# shield3.net
KiCad netlist of a schematic drawn in EAGLE
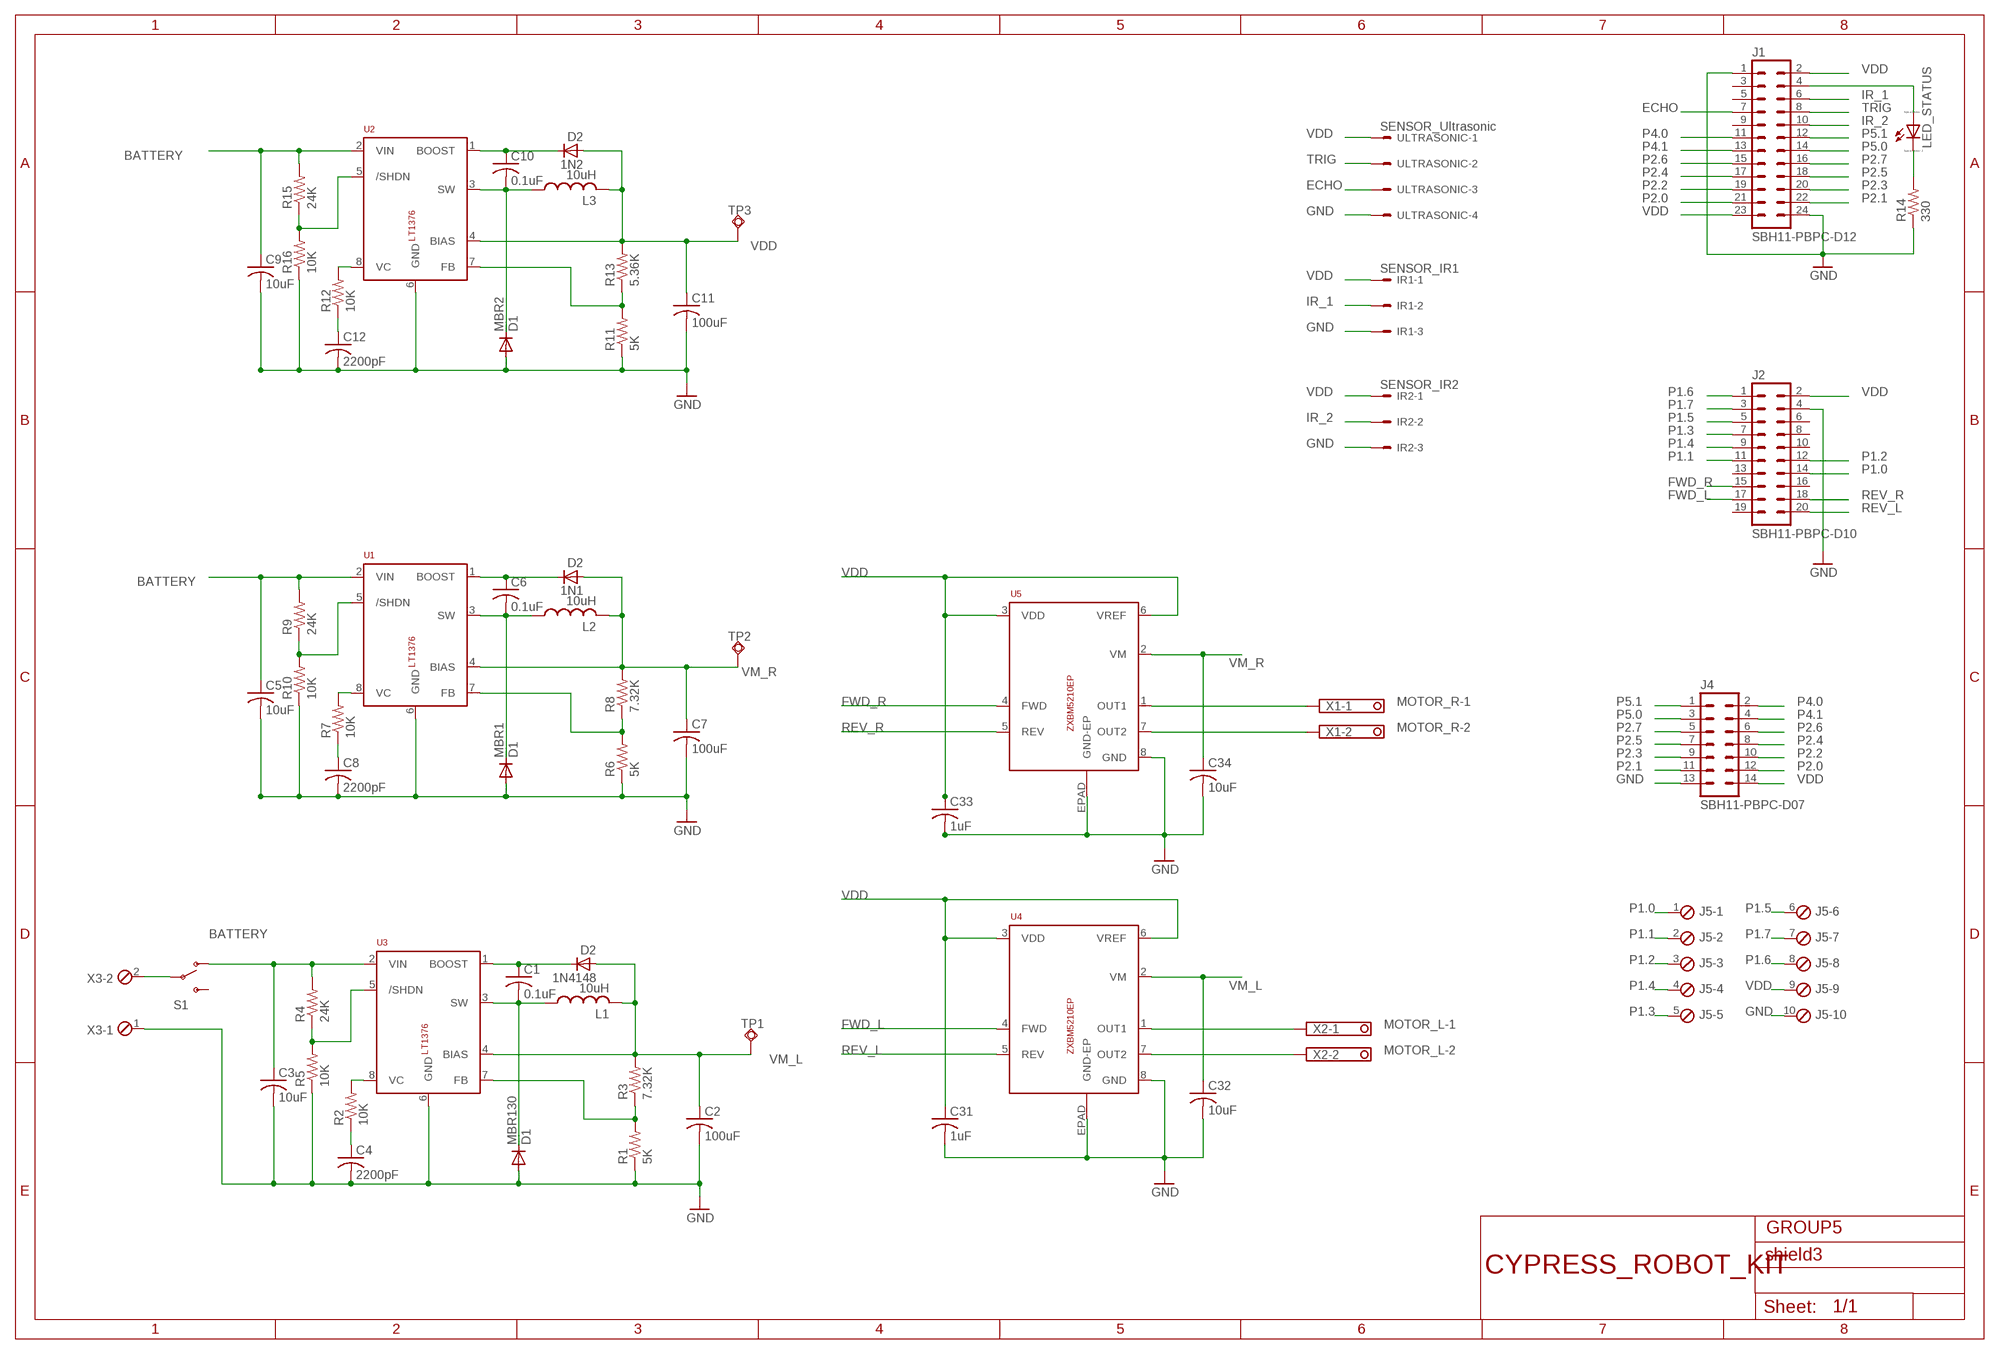
[diagram p0: schematic, sheet 1]

(export (version "E")
  (design (tool "Eeschema 10.0.6"))
  (components
    (comp (ref "1N1")
      (value "D2")
      (footprint "eagle-import:SOD123")
      (libsource (lib "eagle-import") (part "D-SOD123"))
    )
    (comp (ref "1N2")
      (value "D2")
      (footprint "eagle-import:SOD123")
      (libsource (lib "eagle-import") (part "D-SOD123"))
    )
    (comp (ref "1N4148")
      (value "D2")
      (footprint "eagle-import:SOD123")
      (libsource (lib "eagle-import") (part "D-SOD123"))
    )
    (comp (ref "C1")
      (value "0.1uF")
      (footprint "eagle-import:C1206")
      (libsource (lib "eagle-import") (part "C-USC1206"))
    )
    (comp (ref "C2")
      (value "100uF")
      (footprint "eagle-import:C1206")
      (libsource (lib "eagle-import") (part "C-USC1206"))
    )
    (comp (ref "C3")
      (value "10uF")
      (footprint "eagle-import:C1206")
      (libsource (lib "eagle-import") (part "C-USC1206"))
    )
    (comp (ref "C4")
      (value "2200pF")
      (footprint "eagle-import:C1206")
      (libsource (lib "eagle-import") (part "C-USC1206"))
    )
    (comp (ref "C5")
      (value "10uF")
      (footprint "eagle-import:C1206")
      (libsource (lib "eagle-import") (part "C-USC1206"))
    )
    (comp (ref "C6")
      (value "0.1uF")
      (footprint "eagle-import:C1206")
      (libsource (lib "eagle-import") (part "C-USC1206"))
    )
    (comp (ref "C7")
      (value "100uF")
      (footprint "eagle-import:C1206")
      (libsource (lib "eagle-import") (part "C-USC1206"))
    )
    (comp (ref "C8")
      (value "2200pF")
      (footprint "eagle-import:C1206")
      (libsource (lib "eagle-import") (part "C-USC1206"))
    )
    (comp (ref "C9")
      (value "10uF")
      (footprint "eagle-import:C1206")
      (libsource (lib "eagle-import") (part "C-USC1206"))
    )
    (comp (ref "C10")
      (value "0.1uF")
      (footprint "eagle-import:C1206")
      (libsource (lib "eagle-import") (part "C-USC1206"))
    )
    (comp (ref "C11")
      (value "100uF")
      (footprint "eagle-import:C1206")
      (libsource (lib "eagle-import") (part "C-USC1206"))
    )
    (comp (ref "C12")
      (value "2200pF")
      (footprint "eagle-import:C1206")
      (libsource (lib "eagle-import") (part "C-USC1206"))
    )
    (comp (ref "C31")
      (value "1uF")
      (footprint "eagle-import:C3216")
      (libsource (lib "eagle-import") (part "C-USC3216"))
    )
    (comp (ref "C32")
      (value "10uF")
      (footprint "eagle-import:C3216")
      (libsource (lib "eagle-import") (part "C-USC3216"))
    )
    (comp (ref "C33")
      (value "1uF")
      (footprint "eagle-import:C3216")
      (libsource (lib "eagle-import") (part "C-USC3216"))
    )
    (comp (ref "C34")
      (value "10uF")
      (footprint "eagle-import:C3216")
      (libsource (lib "eagle-import") (part "C-USC3216"))
    )
    (comp (ref "IR1")
      (value "SENSOR_IR1")
      (footprint "eagle-import:6410-03")
      (libsource (lib "eagle-import") (part "22-?-0327-2031"))
    )
    (comp (ref "IR2")
      (value "SENSOR_IR2")
      (footprint "eagle-import:6410-03")
      (libsource (lib "eagle-import") (part "22-?-0327-2031"))
    )
    (comp (ref "J1")
      (value "SBH11-PBPC-D12")
      (footprint "eagle-import:SBH11-PBPC-D12")
      (libsource (lib "eagle-import") (part "SBH11-PBPC-D12"))
    )
    (comp (ref "J2")
      (value "SBH11-PBPC-D10")
      (footprint "eagle-import:SBH11-PBPC-D10")
      (libsource (lib "eagle-import") (part "SBH11-PBPC-D10"))
    )
    (comp (ref "J4")
      (value "SBH11-PBPC-D07")
      (footprint "eagle-import:SBH11-PBPC-D07")
      (libsource (lib "eagle-import") (part "SBH11-PBPC-D07"))
    )
    (comp (ref "J5")
      (value "MPT10")
      (footprint "eagle-import:10POL254")
      (libsource (lib "eagle-import") (part "MPT10"))
    )
    (comp (ref "L1")
      (value "10uH")
      (footprint "eagle-import:L4035M")
      (libsource (lib "eagle-import") (part "L-USL4035M"))
    )
    (comp (ref "L2")
      (value "10uH")
      (footprint "eagle-import:L4035M")
      (libsource (lib "eagle-import") (part "L-USL4035M"))
    )
    (comp (ref "L3")
      (value "10uH")
      (footprint "eagle-import:L4035M")
      (libsource (lib "eagle-import") (part "L-USL4035M"))
    )
    (comp (ref "LED_STATUS")
      (value "LED_E")
      (footprint "eagle-import:LED_1206")
      (libsource (lib "eagle-import") (part "LED_E"))
    )
    (comp (ref "MBR1")
      (value "D1")
      (footprint "eagle-import:SOD123")
      (libsource (lib "eagle-import") (part "DIODE-SOD123"))
    )
    (comp (ref "MBR2")
      (value "D1")
      (footprint "eagle-import:SOD123")
      (libsource (lib "eagle-import") (part "DIODE-SOD123"))
    )
    (comp (ref "MBR130")
      (value "D1")
      (footprint "eagle-import:SOD123")
      (libsource (lib "eagle-import") (part "DIODE-SOD123"))
    )
    (comp (ref "R1")
      (value "5K")
      (footprint "eagle-import:M3216")
      (libsource (lib "eagle-import") (part "R-US_M3216"))
    )
    (comp (ref "R2")
      (value "10K")
      (footprint "eagle-import:M3216")
      (libsource (lib "eagle-import") (part "R-US_M3216"))
    )
    (comp (ref "R3")
      (value "7.32K")
      (footprint "eagle-import:M3216")
      (libsource (lib "eagle-import") (part "R-US_M3216"))
    )
    (comp (ref "R4")
      (value "24K")
      (footprint "eagle-import:M3216")
      (libsource (lib "eagle-import") (part "R-US_M3216"))
    )
    (comp (ref "R5")
      (value "10K")
      (footprint "eagle-import:M3216")
      (libsource (lib "eagle-import") (part "R-US_M3216"))
    )
    (comp (ref "R6")
      (value "5K")
      (footprint "eagle-import:M3216")
      (libsource (lib "eagle-import") (part "R-US_M3216"))
    )
    (comp (ref "R7")
      (value "10K")
      (footprint "eagle-import:M3216")
      (libsource (lib "eagle-import") (part "R-US_M3216"))
    )
    (comp (ref "R8")
      (value "7.32K")
      (footprint "eagle-import:M3216")
      (libsource (lib "eagle-import") (part "R-US_M3216"))
    )
    (comp (ref "R9")
      (value "24K")
      (footprint "eagle-import:M3216")
      (libsource (lib "eagle-import") (part "R-US_M3216"))
    )
    (comp (ref "R10")
      (value "10K")
      (footprint "eagle-import:M3216")
      (libsource (lib "eagle-import") (part "R-US_M3216"))
    )
    (comp (ref "R11")
      (value "5K")
      (footprint "eagle-import:M3216")
      (libsource (lib "eagle-import") (part "R-US_M3216"))
    )
    (comp (ref "R12")
      (value "10K")
      (footprint "eagle-import:M3216")
      (libsource (lib "eagle-import") (part "R-US_M3216"))
    )
    (comp (ref "R13")
      (value "5.36K")
      (footprint "eagle-import:M3216")
      (libsource (lib "eagle-import") (part "R-US_M3216"))
    )
    (comp (ref "R14")
      (value "330")
      (footprint "eagle-import:M3216")
      (libsource (lib "eagle-import") (part "resistor_R-US_M3216"))
    )
    (comp (ref "R15")
      (value "24K")
      (footprint "eagle-import:M3216")
      (libsource (lib "eagle-import") (part "R-US_M3216"))
    )
    (comp (ref "R16")
      (value "10K")
      (footprint "eagle-import:M3216")
      (libsource (lib "eagle-import") (part "R-US_M3216"))
    )
    (comp (ref "S1")
      (value "SWITCH-SPDTPTH")
      (footprint "eagle-import:SWITCH-SPDT")
      (libsource (lib "eagle-import") (part "SWITCH-SPDTPTH"))
    )
    (comp (ref "TP1")
      (value "TPSQPAD1-13")
      (footprint "eagle-import:P1-13")
      (libsource (lib "eagle-import") (part "TPSQPAD1-13"))
    )
    (comp (ref "TP2")
      (value "TPSQPAD1-13")
      (footprint "eagle-import:P1-13")
      (libsource (lib "eagle-import") (part "TPSQPAD1-13"))
    )
    (comp (ref "TP3")
      (value "TPSQPAD1-13")
      (footprint "eagle-import:P1-13")
      (libsource (lib "eagle-import") (part "TPSQPAD1-13"))
    )
    (comp (ref "U1")
      (value "LT1376")
      (footprint "eagle-import:S8")
      (libsource (lib "eagle-import") (part "LT1376"))
    )
    (comp (ref "U2")
      (value "LT1376")
      (footprint "eagle-import:S8")
      (libsource (lib "eagle-import") (part "LT1376"))
    )
    (comp (ref "U3")
      (value "LT1376")
      (footprint "eagle-import:S8")
      (libsource (lib "eagle-import") (part "LT1376"))
    )
    (comp (ref "U4")
      (value "ZXBM5210EP")
      (footprint "eagle-import:SO08-EPAD")
      (libsource (lib "eagle-import") (part "ZXBM5210EP"))
    )
    (comp (ref "U5")
      (value "ZXBM5210EP")
      (footprint "eagle-import:SO08-EPAD")
      (libsource (lib "eagle-import") (part "ZXBM5210EP"))
    )
    (comp (ref "ULTRASONIC")
      (value "SENSOR_Ultrasonic")
      (footprint "eagle-import:6410-04")
      (libsource (lib "eagle-import") (part "22-?-0427-2041"))
    )
    (comp (ref "X1")
      (value "1751248")
      (footprint "eagle-import:1751248")
      (libsource (lib "eagle-import") (part "1751248"))
    )
    (comp (ref "X2")
      (value "1751248")
      (footprint "eagle-import:1751248")
      (libsource (lib "eagle-import") (part "1751248"))
    )
    (comp (ref "X3")
      (value "MPT2")
      (footprint "eagle-import:2POL254")
      (libsource (lib "eagle-import") (part "MPT2"))
    )
  )
  (nets
    (net (code "1") (name "/BATTERY") (class "Default")
      (node (ref "C3") (pin "1") (pinfunction "1_1") (pintype "passive"))
      (node (ref "C5") (pin "1") (pinfunction "1_1") (pintype "passive"))
      (node (ref "C9") (pin "1") (pinfunction "1_1") (pintype "passive"))
      (node (ref "R15") (pin "2") (pinfunction "2_2") (pintype "passive"))
      (node (ref "R4") (pin "2") (pinfunction "2_2") (pintype "passive"))
      (node (ref "R9") (pin "2") (pinfunction "2_2") (pintype "passive"))
      (node (ref "S1") (pin "1") (pinfunction "O_1") (pintype "passive"))
      (node (ref "U1") (pin "2") (pinfunction "VIN_2") (pintype "bidirectional"))
      (node (ref "U2") (pin "2") (pinfunction "VIN_2") (pintype "bidirectional"))
      (node (ref "U3") (pin "2") (pinfunction "VIN_2") (pintype "bidirectional"))
    )
    (net (code "2") (name "/ECHO") (class "Default")
      (node (ref "J1") (pin "7") (pinfunction "7_7") (pintype "passive"))
      (node (ref "ULTRASONIC") (pin "3") (pinfunction "S_3") (pintype "passive"))
    )
    (net (code "3") (name "/FWD_L") (class "Default")
      (node (ref "J2") (pin "17") (pinfunction "17_17") (pintype "passive"))
      (node (ref "U4") (pin "4") (pinfunction "FWD_4") (pintype "bidirectional"))
    )
    (net (code "4") (name "/FWD_R") (class "Default")
      (node (ref "J2") (pin "15") (pinfunction "15_15") (pintype "passive"))
      (node (ref "U5") (pin "4") (pinfunction "FWD_4") (pintype "bidirectional"))
    )
    (net (code "5") (name "/IR_1") (class "Default")
      (node (ref "IR1") (pin "2") (pinfunction "S_2") (pintype "passive"))
      (node (ref "J1") (pin "6") (pinfunction "6_6") (pintype "passive"))
    )
    (net (code "6") (name "/IR_2") (class "Default")
      (node (ref "IR2") (pin "2") (pinfunction "S_2") (pintype "passive"))
      (node (ref "J1") (pin "10") (pinfunction "10_10") (pintype "passive"))
    )
    (net (code "7") (name "/MOTOR_L-1") (class "Default")
      (node (ref "U4") (pin "1") (pinfunction "OUT1_1") (pintype "bidirectional"))
      (node (ref "X2") (pin "1") (pinfunction "K_1") (pintype "passive"))
    )
    (net (code "8") (name "/MOTOR_L-2") (class "Default")
      (node (ref "U4") (pin "7") (pinfunction "OUT2_7") (pintype "bidirectional"))
      (node (ref "X2") (pin "2") (pinfunction "K_2") (pintype "passive"))
    )
    (net (code "9") (name "/MOTOR_R-1") (class "Default")
      (node (ref "U5") (pin "1") (pinfunction "OUT1_1") (pintype "bidirectional"))
      (node (ref "X1") (pin "1") (pinfunction "K_1") (pintype "passive"))
    )
    (net (code "10") (name "/MOTOR_R-2") (class "Default")
      (node (ref "U5") (pin "7") (pinfunction "OUT2_7") (pintype "bidirectional"))
      (node (ref "X1") (pin "2") (pinfunction "K_2") (pintype "passive"))
    )
    (net (code "11") (name "/P1.0") (class "Default")
      (node (ref "J2") (pin "14") (pinfunction "14_14") (pintype "passive"))
      (node (ref "J5") (pin "1") (pinfunction "1_1") (pintype "passive"))
    )
    (net (code "12") (name "/P1.1") (class "Default")
      (node (ref "J2") (pin "11") (pinfunction "11_11") (pintype "passive"))
      (node (ref "J5") (pin "2") (pinfunction "1_2") (pintype "passive"))
    )
    (net (code "13") (name "/P1.2") (class "Default")
      (node (ref "J2") (pin "12") (pinfunction "12_12") (pintype "passive"))
      (node (ref "J5") (pin "3") (pinfunction "1_3") (pintype "passive"))
    )
    (net (code "14") (name "/P1.3") (class "Default")
      (node (ref "J2") (pin "7") (pinfunction "7_7") (pintype "passive"))
      (node (ref "J5") (pin "5") (pinfunction "1_5") (pintype "passive"))
    )
    (net (code "15") (name "/P1.4") (class "Default")
      (node (ref "J2") (pin "9") (pinfunction "9_9") (pintype "passive"))
      (node (ref "J5") (pin "4") (pinfunction "1_4") (pintype "passive"))
    )
    (net (code "16") (name "/P1.5") (class "Default")
      (node (ref "J2") (pin "5") (pinfunction "5_5") (pintype "passive"))
      (node (ref "J5") (pin "6") (pinfunction "1_6") (pintype "passive"))
    )
    (net (code "17") (name "/P1.6") (class "Default")
      (node (ref "J2") (pin "1") (pinfunction "1_1") (pintype "passive"))
      (node (ref "J5") (pin "8") (pinfunction "1_8") (pintype "passive"))
    )
    (net (code "18") (name "/P1.7") (class "Default")
      (node (ref "J2") (pin "3") (pinfunction "3_3") (pintype "passive"))
      (node (ref "J5") (pin "7") (pinfunction "1_7") (pintype "passive"))
    )
    (net (code "19") (name "/P2.0") (class "Default")
      (node (ref "J1") (pin "21") (pinfunction "21_21") (pintype "passive"))
      (node (ref "J4") (pin "12") (pinfunction "12_12") (pintype "passive"))
    )
    (net (code "20") (name "/P2.1") (class "Default")
      (node (ref "J1") (pin "22") (pinfunction "22_22") (pintype "passive"))
      (node (ref "J4") (pin "11") (pinfunction "11_11") (pintype "passive"))
    )
    (net (code "21") (name "/P2.2") (class "Default")
      (node (ref "J1") (pin "19") (pinfunction "19_19") (pintype "passive"))
      (node (ref "J4") (pin "10") (pinfunction "10_10") (pintype "passive"))
    )
    (net (code "22") (name "/P2.3") (class "Default")
      (node (ref "J1") (pin "20") (pinfunction "20_20") (pintype "passive"))
      (node (ref "J4") (pin "9") (pinfunction "9_9") (pintype "passive"))
    )
    (net (code "23") (name "/P2.4") (class "Default")
      (node (ref "J1") (pin "17") (pinfunction "17_17") (pintype "passive"))
      (node (ref "J4") (pin "8") (pinfunction "8_8") (pintype "passive"))
    )
    (net (code "24") (name "/P2.5") (class "Default")
      (node (ref "J1") (pin "18") (pinfunction "18_18") (pintype "passive"))
      (node (ref "J4") (pin "7") (pinfunction "7_7") (pintype "passive"))
    )
    (net (code "25") (name "/P2.6") (class "Default")
      (node (ref "J1") (pin "15") (pinfunction "15_15") (pintype "passive"))
      (node (ref "J4") (pin "6") (pinfunction "6_6") (pintype "passive"))
    )
    (net (code "26") (name "/P2.7") (class "Default")
      (node (ref "J1") (pin "16") (pinfunction "16_16") (pintype "passive"))
      (node (ref "J4") (pin "5") (pinfunction "5_5") (pintype "passive"))
    )
    (net (code "27") (name "/P4.0") (class "Default")
      (node (ref "J1") (pin "11") (pinfunction "11_11") (pintype "passive"))
      (node (ref "J4") (pin "2") (pinfunction "2_2") (pintype "passive"))
    )
    (net (code "28") (name "/P4.1") (class "Default")
      (node (ref "J1") (pin "13") (pinfunction "13_13") (pintype "passive"))
      (node (ref "J4") (pin "4") (pinfunction "4_4") (pintype "passive"))
    )
    (net (code "29") (name "/P5.0") (class "Default")
      (node (ref "J1") (pin "14") (pinfunction "14_14") (pintype "passive"))
      (node (ref "J4") (pin "3") (pinfunction "3_3") (pintype "passive"))
    )
    (net (code "30") (name "/P5.1") (class "Default")
      (node (ref "J1") (pin "12") (pinfunction "12_12") (pintype "passive"))
      (node (ref "J4") (pin "1") (pinfunction "1_1") (pintype "passive"))
    )
    (net (code "31") (name "/REV_L") (class "Default")
      (node (ref "J2") (pin "20") (pinfunction "20_20") (pintype "passive"))
      (node (ref "U4") (pin "5") (pinfunction "REV_5") (pintype "bidirectional"))
    )
    (net (code "32") (name "/REV_R") (class "Default")
      (node (ref "J2") (pin "18") (pinfunction "18_18") (pintype "passive"))
      (node (ref "U5") (pin "5") (pinfunction "REV_5") (pintype "bidirectional"))
    )
    (net (code "33") (name "/TRIG") (class "Default")
      (node (ref "J1") (pin "8") (pinfunction "8_8") (pintype "passive"))
      (node (ref "ULTRASONIC") (pin "2") (pinfunction "S_2") (pintype "passive"))
    )
    (net (code "34") (name "/VDD") (class "Default")
      (node (ref "1N2") (pin "2") (pinfunction "A_2") (pintype "passive"))
      (node (ref "C11") (pin "1") (pinfunction "1_1") (pintype "passive"))
      (node (ref "C31") (pin "1") (pinfunction "1_1") (pintype "passive"))
      (node (ref "C33") (pin "1") (pinfunction "1_1") (pintype "passive"))
      (node (ref "IR1") (pin "1") (pinfunction "S_1") (pintype "passive"))
      (node (ref "IR2") (pin "1") (pinfunction "S_1") (pintype "passive"))
      (node (ref "J1") (pin "2") (pinfunction "2_2") (pintype "passive"))
      (node (ref "J1") (pin "23") (pinfunction "23_23") (pintype "passive"))
      (node (ref "J2") (pin "2") (pinfunction "2_2") (pintype "passive"))
      (node (ref "J4") (pin "14") (pinfunction "14_14") (pintype "passive"))
      (node (ref "J5") (pin "9") (pinfunction "1_9") (pintype "passive"))
      (node (ref "L3") (pin "2") (pinfunction "2_2") (pintype "passive"))
      (node (ref "R13") (pin "2") (pinfunction "2_2") (pintype "passive"))
      (node (ref "TP3") (pin "TP") (pinfunction "TP_TP") (pintype "input"))
      (node (ref "U2") (pin "4") (pinfunction "BIAS_4") (pintype "bidirectional"))
      (node (ref "U4") (pin "3") (pinfunction "VDD_3") (pintype "bidirectional"))
      (node (ref "U4") (pin "6") (pinfunction "VREF_6") (pintype "bidirectional"))
      (node (ref "U5") (pin "3") (pinfunction "VDD_3") (pintype "bidirectional"))
      (node (ref "U5") (pin "6") (pinfunction "VREF_6") (pintype "bidirectional"))
      (node (ref "ULTRASONIC") (pin "1") (pinfunction "S_1") (pintype "passive"))
    )
    (net (code "35") (name "/VM_L") (class "Default")
      (node (ref "1N4148") (pin "2") (pinfunction "A_2") (pintype "passive"))
      (node (ref "C2") (pin "1") (pinfunction "1_1") (pintype "passive"))
      (node (ref "C32") (pin "1") (pinfunction "1_1") (pintype "passive"))
      (node (ref "L1") (pin "2") (pinfunction "2_2") (pintype "passive"))
      (node (ref "R3") (pin "2") (pinfunction "2_2") (pintype "passive"))
      (node (ref "TP1") (pin "TP") (pinfunction "TP_TP") (pintype "input"))
      (node (ref "U3") (pin "4") (pinfunction "BIAS_4") (pintype "bidirectional"))
      (node (ref "U4") (pin "2") (pinfunction "VM_2") (pintype "bidirectional"))
    )
    (net (code "36") (name "/VM_R") (class "Default")
      (node (ref "1N1") (pin "2") (pinfunction "A_2") (pintype "passive"))
      (node (ref "C34") (pin "1") (pinfunction "1_1") (pintype "passive"))
      (node (ref "C7") (pin "1") (pinfunction "1_1") (pintype "passive"))
      (node (ref "L2") (pin "2") (pinfunction "2_2") (pintype "passive"))
      (node (ref "R8") (pin "2") (pinfunction "2_2") (pintype "passive"))
      (node (ref "TP2") (pin "TP") (pinfunction "TP_TP") (pintype "input"))
      (node (ref "U1") (pin "4") (pinfunction "BIAS_4") (pintype "bidirectional"))
      (node (ref "U5") (pin "2") (pinfunction "VM_2") (pintype "bidirectional"))
    )
    (net (code "37") (name "GND") (class "Default")
      (node (ref "C11") (pin "2") (pinfunction "2_2") (pintype "passive"))
      (node (ref "C12") (pin "2") (pinfunction "2_2") (pintype "passive"))
      (node (ref "C2") (pin "2") (pinfunction "2_2") (pintype "passive"))
      (node (ref "C3") (pin "2") (pinfunction "2_2") (pintype "passive"))
      (node (ref "C31") (pin "2") (pinfunction "2_2") (pintype "passive"))
      (node (ref "C32") (pin "2") (pinfunction "2_2") (pintype "passive"))
      (node (ref "C33") (pin "2") (pinfunction "2_2") (pintype "passive"))
      (node (ref "C34") (pin "2") (pinfunction "2_2") (pintype "passive"))
      (node (ref "C4") (pin "2") (pinfunction "2_2") (pintype "passive"))
      (node (ref "C5") (pin "2") (pinfunction "2_2") (pintype "passive"))
      (node (ref "C7") (pin "2") (pinfunction "2_2") (pintype "passive"))
      (node (ref "C8") (pin "2") (pinfunction "2_2") (pintype "passive"))
      (node (ref "C9") (pin "2") (pinfunction "2_2") (pintype "passive"))
      (node (ref "IR1") (pin "3") (pinfunction "S_3") (pintype "passive"))
      (node (ref "IR2") (pin "3") (pinfunction "S_3") (pintype "passive"))
      (node (ref "J1") (pin "1") (pinfunction "1_1") (pintype "passive"))
      (node (ref "J1") (pin "24") (pinfunction "24_24") (pintype "passive"))
      (node (ref "J2") (pin "4") (pinfunction "4_4") (pintype "passive"))
      (node (ref "J4") (pin "13") (pinfunction "13_13") (pintype "passive"))
      (node (ref "J5") (pin "10") (pinfunction "1_10") (pintype "passive"))
      (node (ref "MBR1") (pin "A") (pinfunction "A_A") (pintype "passive"))
      (node (ref "MBR130") (pin "A") (pinfunction "A_A") (pintype "passive"))
      (node (ref "MBR2") (pin "A") (pinfunction "A_A") (pintype "passive"))
      (node (ref "R1") (pin "1") (pinfunction "1_1") (pintype "passive"))
      (node (ref "R10") (pin "1") (pinfunction "1_1") (pintype "passive"))
      (node (ref "R11") (pin "1") (pinfunction "1_1") (pintype "passive"))
      (node (ref "R14") (pin "1") (pinfunction "1_1") (pintype "passive"))
      (node (ref "R16") (pin "1") (pinfunction "1_1") (pintype "passive"))
      (node (ref "R5") (pin "1") (pinfunction "1_1") (pintype "passive"))
      (node (ref "R6") (pin "1") (pinfunction "1_1") (pintype "passive"))
      (node (ref "U1") (pin "6") (pinfunction "GND_6") (pintype "bidirectional"))
      (node (ref "U2") (pin "6") (pinfunction "GND_6") (pintype "bidirectional"))
      (node (ref "U3") (pin "6") (pinfunction "GND_6") (pintype "bidirectional"))
      (node (ref "U4") (pin "8") (pinfunction "GND_8") (pintype "bidirectional"))
      (node (ref "U4") (pin "EPAD") (pinfunction "GND-EP_EPAD") (pintype "bidirectional"))
      (node (ref "U5") (pin "8") (pinfunction "GND_8") (pintype "bidirectional"))
      (node (ref "U5") (pin "EPAD") (pinfunction "GND-EP_EPAD") (pintype "bidirectional"))
      (node (ref "ULTRASONIC") (pin "4") (pinfunction "S_4") (pintype "passive"))
      (node (ref "X3") (pin "1") (pinfunction "1_1") (pintype "passive"))
    )
    (net (code "38") (name "Net-(1N1-C)") (class "Default")
      (node (ref "1N1") (pin "1") (pinfunction "C_1") (pintype "passive"))
      (node (ref "C6") (pin "1") (pinfunction "1_1") (pintype "passive"))
      (node (ref "U1") (pin "1") (pinfunction "BOOST_1") (pintype "bidirectional"))
    )
    (net (code "39") (name "Net-(1N2-C)") (class "Default")
      (node (ref "1N2") (pin "1") (pinfunction "C_1") (pintype "passive"))
      (node (ref "C10") (pin "1") (pinfunction "1_1") (pintype "passive"))
      (node (ref "U2") (pin "1") (pinfunction "BOOST_1") (pintype "bidirectional"))
    )
    (net (code "40") (name "Net-(1N4148-C)") (class "Default")
      (node (ref "1N4148") (pin "1") (pinfunction "C_1") (pintype "passive"))
      (node (ref "C1") (pin "1") (pinfunction "1_1") (pintype "passive"))
      (node (ref "U3") (pin "1") (pinfunction "BOOST_1") (pintype "bidirectional"))
    )
    (net (code "41") (name "Net-(C4-Pad1)") (class "Default")
      (node (ref "C4") (pin "1") (pinfunction "1_1") (pintype "passive"))
      (node (ref "R2") (pin "1") (pinfunction "1_1") (pintype "passive"))
    )
    (net (code "42") (name "Net-(C8-Pad1)") (class "Default")
      (node (ref "C8") (pin "1") (pinfunction "1_1") (pintype "passive"))
      (node (ref "R7") (pin "1") (pinfunction "1_1") (pintype "passive"))
    )
    (net (code "43") (name "Net-(C12-Pad1)") (class "Default")
      (node (ref "C12") (pin "1") (pinfunction "1_1") (pintype "passive"))
      (node (ref "R12") (pin "1") (pinfunction "1_1") (pintype "passive"))
    )
    (net (code "44") (name "Net-(J1-Pad4)") (class "Default")
      (node (ref "J1") (pin "4") (pinfunction "4_4") (pintype "passive"))
      (node (ref "LED_STATUS") (pin "A") (pinfunction "A_A") (pintype "passive"))
    )
    (net (code "45") (name "Net-(LED_STATUS-PadC)") (class "Default")
      (node (ref "LED_STATUS") (pin "C") (pinfunction "C_C") (pintype "passive"))
      (node (ref "R14") (pin "2") (pinfunction "2_2") (pintype "passive"))
    )
    (net (code "46") (name "Net-(S1-P)") (class "Default")
      (node (ref "S1") (pin "2") (pinfunction "P_2") (pintype "passive"))
      (node (ref "X3") (pin "2") (pinfunction "1_2") (pintype "passive"))
    )
    (net (code "47") (name "Net-(U1-FB)") (class "Default")
      (node (ref "R6") (pin "2") (pinfunction "2_2") (pintype "passive"))
      (node (ref "R8") (pin "1") (pinfunction "1_1") (pintype "passive"))
      (node (ref "U1") (pin "7") (pinfunction "FB_7") (pintype "bidirectional"))
    )
    (net (code "48") (name "Net-(U1-SW)") (class "Default")
      (node (ref "C6") (pin "2") (pinfunction "2_2") (pintype "passive"))
      (node (ref "L2") (pin "1") (pinfunction "1_1") (pintype "passive"))
      (node (ref "MBR1") (pin "C") (pinfunction "C_C") (pintype "passive"))
      (node (ref "U1") (pin "3") (pinfunction "SW_3") (pintype "bidirectional"))
    )
    (net (code "49") (name "Net-(U1-VC)") (class "Default")
      (node (ref "R7") (pin "2") (pinfunction "2_2") (pintype "passive"))
      (node (ref "U1") (pin "8") (pinfunction "VC_8") (pintype "bidirectional"))
    )
    (net (code "50") (name "Net-(U1-{slash}SHDN)") (class "Default")
      (node (ref "R10") (pin "2") (pinfunction "2_2") (pintype "passive"))
      (node (ref "R9") (pin "1") (pinfunction "1_1") (pintype "passive"))
      (node (ref "U1") (pin "5") (pinfunction "/SHDN_5") (pintype "bidirectional"))
    )
    (net (code "51") (name "Net-(U2-FB)") (class "Default")
      (node (ref "R11") (pin "2") (pinfunction "2_2") (pintype "passive"))
      (node (ref "R13") (pin "1") (pinfunction "1_1") (pintype "passive"))
      (node (ref "U2") (pin "7") (pinfunction "FB_7") (pintype "bidirectional"))
    )
    (net (code "52") (name "Net-(U2-SW)") (class "Default")
      (node (ref "C10") (pin "2") (pinfunction "2_2") (pintype "passive"))
      (node (ref "L3") (pin "1") (pinfunction "1_1") (pintype "passive"))
      (node (ref "MBR2") (pin "C") (pinfunction "C_C") (pintype "passive"))
      (node (ref "U2") (pin "3") (pinfunction "SW_3") (pintype "bidirectional"))
    )
    (net (code "53") (name "Net-(U2-VC)") (class "Default")
      (node (ref "R12") (pin "2") (pinfunction "2_2") (pintype "passive"))
      (node (ref "U2") (pin "8") (pinfunction "VC_8") (pintype "bidirectional"))
    )
    (net (code "54") (name "Net-(U2-{slash}SHDN)") (class "Default")
      (node (ref "R15") (pin "1") (pinfunction "1_1") (pintype "passive"))
      (node (ref "R16") (pin "2") (pinfunction "2_2") (pintype "passive"))
      (node (ref "U2") (pin "5") (pinfunction "/SHDN_5") (pintype "bidirectional"))
    )
    (net (code "55") (name "Net-(U3-FB)") (class "Default")
      (node (ref "R1") (pin "2") (pinfunction "2_2") (pintype "passive"))
      (node (ref "R3") (pin "1") (pinfunction "1_1") (pintype "passive"))
      (node (ref "U3") (pin "7") (pinfunction "FB_7") (pintype "bidirectional"))
    )
    (net (code "56") (name "Net-(U3-SW)") (class "Default")
      (node (ref "C1") (pin "2") (pinfunction "2_2") (pintype "passive"))
      (node (ref "L1") (pin "1") (pinfunction "1_1") (pintype "passive"))
      (node (ref "MBR130") (pin "C") (pinfunction "C_C") (pintype "passive"))
      (node (ref "U3") (pin "3") (pinfunction "SW_3") (pintype "bidirectional"))
    )
    (net (code "57") (name "Net-(U3-VC)") (class "Default")
      (node (ref "R2") (pin "2") (pinfunction "2_2") (pintype "passive"))
      (node (ref "U3") (pin "8") (pinfunction "VC_8") (pintype "bidirectional"))
    )
    (net (code "58") (name "Net-(U3-{slash}SHDN)") (class "Default")
      (node (ref "R4") (pin "1") (pinfunction "1_1") (pintype "passive"))
      (node (ref "R5") (pin "2") (pinfunction "2_2") (pintype "passive"))
      (node (ref "U3") (pin "5") (pinfunction "/SHDN_5") (pintype "bidirectional"))
    )
    (net (code "59") (name "unconnected-(J1-Pad3)") (class "Default")
      (node (ref "J1") (pin "3") (pinfunction "3_3") (pintype "passive"))
    )
    (net (code "60") (name "unconnected-(J1-Pad5)") (class "Default")
      (node (ref "J1") (pin "5") (pinfunction "5_5") (pintype "passive"))
    )
    (net (code "61") (name "unconnected-(J1-Pad9)") (class "Default")
      (node (ref "J1") (pin "9") (pinfunction "9_9") (pintype "passive"))
    )
    (net (code "62") (name "unconnected-(J2-Pad6)") (class "Default")
      (node (ref "J2") (pin "6") (pinfunction "6_6") (pintype "passive"))
    )
    (net (code "63") (name "unconnected-(J2-Pad8)") (class "Default")
      (node (ref "J2") (pin "8") (pinfunction "8_8") (pintype "passive"))
    )
    (net (code "64") (name "unconnected-(J2-Pad10)") (class "Default")
      (node (ref "J2") (pin "10") (pinfunction "10_10") (pintype "passive"))
    )
    (net (code "65") (name "unconnected-(J2-Pad13)") (class "Default")
      (node (ref "J2") (pin "13") (pinfunction "13_13") (pintype "passive"))
    )
    (net (code "66") (name "unconnected-(J2-Pad16)") (class "Default")
      (node (ref "J2") (pin "16") (pinfunction "16_16") (pintype "passive"))
    )
    (net (code "67") (name "unconnected-(J2-Pad19)") (class "Default")
      (node (ref "J2") (pin "19") (pinfunction "19_19") (pintype "passive"))
    )
    (net (code "68") (name "unconnected-(S1-S-Pad3)") (class "Default")
      (node (ref "S1") (pin "3") (pinfunction "S_3") (pintype "passive"))
    )
  )
)
